# 10_iMX_8X_ETH.net
KiCad netlist of a schematic drawn in Altium Designer
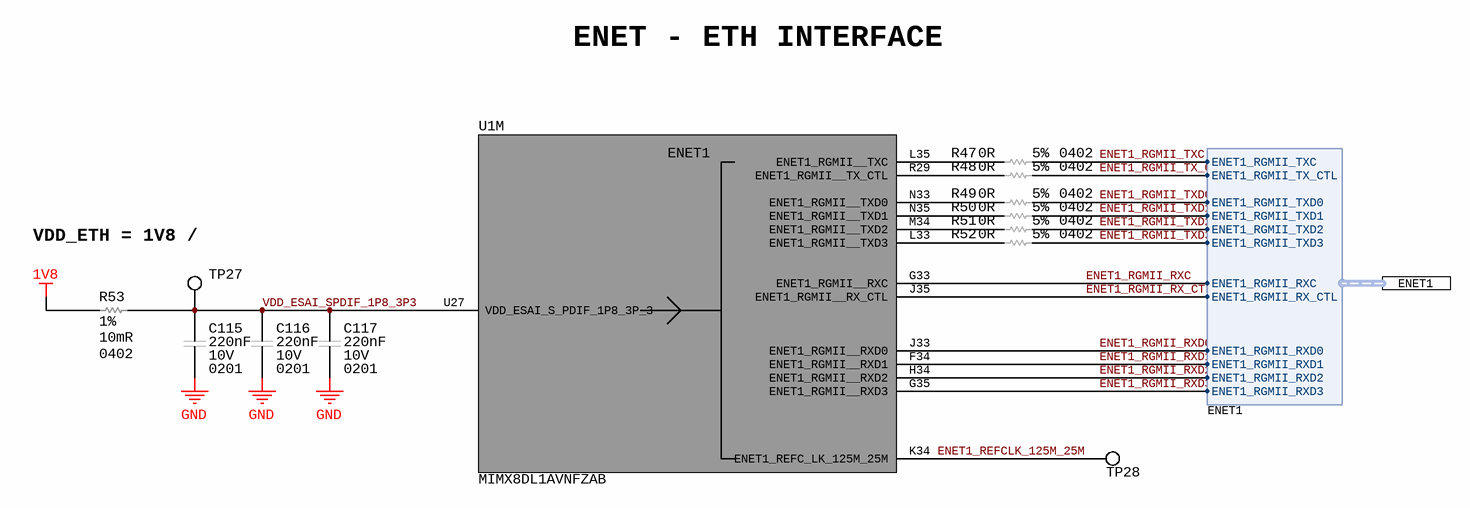
[diagram p0: 10_iMX 8X_ETH.SchDoc]

(export (version "E")
  (design (tool "Eeschema 10.0.6"))
  (components
    (comp (ref "C115")
      (value "LMK063BJ224MP-F")
      (footprint "CAP_0201_CAPC0603X03N")
      (description "Multilayer Ceramic Capacitors (High dielectric type), 10V, 0.22 uF, ± 20 %, 0201, X5R, RoHS")
      (fields
        (field (name "MANUFACTURER") "Taiyo Yuden")
        (field (name "TOLERANCE") "20%")
        (field (name "VOLTAGE RATING (DC)") "10V")
        (field (name "CAPACITANCE") "220nF")
        (field (name "CASE/PACKAGE") "0201")
      )
      (libsource (lib "Electronic Devices_LIB") (part "CAP_0.22UF_10V_X5R_0201"))
    )
    (comp (ref "C116")
      (value "LMK063BJ224MP-F")
      (footprint "CAP_0201_CAPC0603X03N")
      (description "Multilayer Ceramic Capacitors (High dielectric type), 10V, 0.22 uF, ± 20 %, 0201, X5R, RoHS")
      (fields
        (field (name "MANUFACTURER") "Taiyo Yuden")
        (field (name "TOLERANCE") "20%")
        (field (name "VOLTAGE RATING (DC)") "10V")
        (field (name "CAPACITANCE") "220nF")
        (field (name "CASE/PACKAGE") "0201")
      )
      (libsource (lib "Electronic Devices_LIB") (part "CAP_0.22UF_10V_X5R_0201"))
    )
    (comp (ref "C117")
      (value "LMK063BJ224MP-F")
      (footprint "CAP_0201_CAPC0603X03N")
      (description "Multilayer Ceramic Capacitors (High dielectric type), 10V, 0.22 uF, ± 20 %, 0201, X5R, RoHS")
      (fields
        (field (name "MANUFACTURER") "Taiyo Yuden")
        (field (name "TOLERANCE") "20%")
        (field (name "VOLTAGE RATING (DC)") "10V")
        (field (name "CAPACITANCE") "220nF")
        (field (name "CASE/PACKAGE") "0201")
      )
      (libsource (lib "Electronic Devices_LIB") (part "CAP_0.22UF_10V_X5R_0201"))
    )
    (comp (ref "R47")
      (value "ERJ-2GE0R00X")
      (footprint "RES_0402_RESC1005X04N")
      (description "SMD Chip Resistor, Jumper, 0 ohm, 100 mW, 0402 [1005 Metric], Thick Film, General Purpose")
      (fields
        (field (name "MANUFACTURER") "Panasonic")
        (field (name "CASE CODE (IMPERIAL)") "0402")
        (field (name "TOLERANCE") "5%")
        (field (name "RESISTANCE") "0R")
      )
      (libsource (lib "Electronic Devices_LIB") (part "RES_0R_5%_100mW_0402"))
    )
    (comp (ref "R48")
      (value "ERJ-2GE0R00X")
      (footprint "RES_0402_RESC1005X04N")
      (description "SMD Chip Resistor, Jumper, 0 ohm, 100 mW, 0402 [1005 Metric], Thick Film, General Purpose")
      (fields
        (field (name "MANUFACTURER") "Panasonic")
        (field (name "CASE CODE (IMPERIAL)") "0402")
        (field (name "TOLERANCE") "5%")
        (field (name "RESISTANCE") "0R")
      )
      (libsource (lib "Electronic Devices_LIB") (part "RES_0R_5%_100mW_0402"))
    )
    (comp (ref "R49")
      (value "ERJ-2GE0R00X")
      (footprint "RES_0402_RESC1005X04N")
      (description "SMD Chip Resistor, Jumper, 0 ohm, 100 mW, 0402 [1005 Metric], Thick Film, General Purpose")
      (fields
        (field (name "MANUFACTURER") "Panasonic")
        (field (name "CASE CODE (IMPERIAL)") "0402")
        (field (name "TOLERANCE") "5%")
        (field (name "RESISTANCE") "0R")
      )
      (libsource (lib "Electronic Devices_LIB") (part "RES_0R_5%_100mW_0402"))
    )
    (comp (ref "R50")
      (value "ERJ-2GE0R00X")
      (footprint "RES_0402_RESC1005X04N")
      (description "SMD Chip Resistor, Jumper, 0 ohm, 100 mW, 0402 [1005 Metric], Thick Film, General Purpose")
      (fields
        (field (name "MANUFACTURER") "Panasonic")
        (field (name "CASE CODE (IMPERIAL)") "0402")
        (field (name "TOLERANCE") "5%")
        (field (name "RESISTANCE") "0R")
      )
      (libsource (lib "Electronic Devices_LIB") (part "RES_0R_5%_100mW_0402"))
    )
    (comp (ref "R51")
      (value "ERJ-2GE0R00X")
      (footprint "RES_0402_RESC1005X04N")
      (description "SMD Chip Resistor, Jumper, 0 ohm, 100 mW, 0402 [1005 Metric], Thick Film, General Purpose")
      (fields
        (field (name "MANUFACTURER") "Panasonic")
        (field (name "CASE CODE (IMPERIAL)") "0402")
        (field (name "TOLERANCE") "5%")
        (field (name "RESISTANCE") "0R")
      )
      (libsource (lib "Electronic Devices_LIB") (part "RES_0R_5%_100mW_0402"))
    )
    (comp (ref "R52")
      (value "ERJ-2GE0R00X")
      (footprint "RES_0402_RESC1005X04N")
      (description "SMD Chip Resistor, Jumper, 0 ohm, 100 mW, 0402 [1005 Metric], Thick Film, General Purpose")
      (fields
        (field (name "MANUFACTURER") "Panasonic")
        (field (name "CASE CODE (IMPERIAL)") "0402")
        (field (name "TOLERANCE") "5%")
        (field (name "RESISTANCE") "0R")
      )
      (libsource (lib "Electronic Devices_LIB") (part "RES_0R_5%_100mW_0402"))
    )
    (comp (ref "R53")
      (value "ERJ-2LWFR010X")
      (footprint "RES_0603_RESC1608X04N")
      (description "Res Current Sense Thick Film 0402 0.01 Ohm 1% 1/5W 0ppm/°C to 500ppm/°C Molded T/R")
      (fields
        (field (name "MANUFACTURER") "Panasonic")
        (field (name "TOLERANCE") "1%")
        (field (name "RESISTANCE") "10mR")
        (field (name "CASE/PACKAGE") "0402")
      )
      (libsource (lib "Electronic Devices_LIB") (part "RES_10mR_1%_0.05W_0402"))
    )
    (comp (ref "TP27")
      (value "NO COMPONENT")
      (footprint "TP_PAD_0.5MM_SMD_ROUND")
      (description "Test Point, SMD pad, round, 1.5mm, 1.6mm, 3mm diameter")
      (libsource (lib "Electronic Devices_LIB") (part "TP_PAD_SMD_SMALL"))
    )
    (comp (ref "TP28")
      (value "NO COMPONENT")
      (footprint "TP_PAD_0.5MM_SMD_ROUND")
      (description "Test Point, SMD pad, round, 1.5mm, 1.6mm, 3mm diameter")
      (libsource (lib "Electronic Devices_LIB") (part "TP_PAD_SMD_SMALL"))
    )
    (comp (ref "U1")
      (value "MIMX8DL1AVNFZAB")
      (footprint "MIMX8DL1AVNFZAB")
      (description "I.MX8 Dxl 15SQ / Tray Rohs Compliant: Yes")
      (fields (field (name "MANUFACTURER") "NXP Semiconductors"))
      (libsource (lib "Electronic Devices_LIB") (part "IC_MPU_ARM_1.2GHz_MIMX8DL1AVNFZAB"))
    )
  )
  (nets
    (net (code "2") (name "/ENET1_REFCLK_125M_25M") (class "Default")
      (node (ref "TP28") (pin "1") (pinfunction "1_1") (pintype "passive"))
      (node (ref "U1") (pin "K34") (pinfunction "ENET1_REFC_LK_125M_25M_K34") (pintype "passive"))
    )
    (net (code "3") (name "/ENET1_RGMII_RXC") (class "Default")
      (node (ref "U1") (pin "G33") (pinfunction "ENET1_RGMII__RXC_G33") (pintype "passive"))
    )
    (net (code "4") (name "/ENET1_RGMII_RXD0") (class "Default")
      (node (ref "U1") (pin "J33") (pinfunction "ENET1_RGMII__RXD0_J33") (pintype "passive"))
    )
    (net (code "5") (name "/ENET1_RGMII_RXD1") (class "Default")
      (node (ref "U1") (pin "F34") (pinfunction "ENET1_RGMII__RXD1_F34") (pintype "passive"))
    )
    (net (code "6") (name "/ENET1_RGMII_RXD2") (class "Default")
      (node (ref "U1") (pin "H34") (pinfunction "ENET1_RGMII__RXD2_H34") (pintype "passive"))
    )
    (net (code "7") (name "/ENET1_RGMII_RXD3") (class "Default")
      (node (ref "U1") (pin "G35") (pinfunction "ENET1_RGMII__RXD3_G35") (pintype "passive"))
    )
    (net (code "8") (name "/ENET1_RGMII_RX_CTL") (class "Default")
      (node (ref "U1") (pin "J35") (pinfunction "ENET1_RGMII__RX_CTL_J35") (pintype "passive"))
    )
    (net (code "9") (name "/ENET1_RGMII_TXC") (class "Default")
      (node (ref "R47") (pin "2") (pinfunction "2_2") (pintype "passive"))
    )
    (net (code "10") (name "/ENET1_RGMII_TXD0") (class "Default")
      (node (ref "R49") (pin "2") (pinfunction "2_2") (pintype "passive"))
    )
    (net (code "11") (name "/ENET1_RGMII_TXD1") (class "Default")
      (node (ref "R50") (pin "2") (pinfunction "2_2") (pintype "passive"))
    )
    (net (code "12") (name "/ENET1_RGMII_TXD2") (class "Default")
      (node (ref "R51") (pin "2") (pinfunction "2_2") (pintype "passive"))
    )
    (net (code "13") (name "/ENET1_RGMII_TXD3") (class "Default")
      (node (ref "R52") (pin "2") (pinfunction "2_2") (pintype "passive"))
    )
    (net (code "14") (name "/ENET1_RGMII_TX_CTL") (class "Default")
      (node (ref "R48") (pin "2") (pinfunction "2_2") (pintype "passive"))
    )
    (net (code "15") (name "/VDD_ESAI_SPDIF_1P8_3P3") (class "Default")
      (node (ref "C115") (pin "2") (pinfunction "2_2") (pintype "passive"))
      (node (ref "C116") (pin "2") (pinfunction "2_2") (pintype "passive"))
      (node (ref "C117") (pin "2") (pinfunction "2_2") (pintype "passive"))
      (node (ref "R53") (pin "2") (pinfunction "2_2") (pintype "passive"))
      (node (ref "TP27") (pin "1") (pinfunction "1_1") (pintype "passive"))
      (node (ref "U1") (pin "U27") (pinfunction "VDD_ESAI_S_PDIF_1P8_3P_3_U27") (pintype "passive"))
    )
    (net (code "17") (name "1V8") (class "Default")
      (node (ref "R53") (pin "1") (pinfunction "1_1") (pintype "passive"))
    )
    (net (code "18") (name "GND") (class "Default")
      (node (ref "C115") (pin "1") (pinfunction "1_1") (pintype "passive"))
      (node (ref "C116") (pin "1") (pinfunction "1_1") (pintype "passive"))
      (node (ref "C117") (pin "1") (pinfunction "1_1") (pintype "passive"))
    )
    (net (code "19") (name "Net-(U1M-ENET1_RGMII__TXC)") (class "Default")
      (node (ref "R47") (pin "1") (pinfunction "1_1") (pintype "passive"))
      (node (ref "U1") (pin "L35") (pinfunction "ENET1_RGMII__TXC_L35") (pintype "passive"))
    )
    (net (code "20") (name "Net-(U1M-ENET1_RGMII__TXD0)") (class "Default")
      (node (ref "R49") (pin "1") (pinfunction "1_1") (pintype "passive"))
      (node (ref "U1") (pin "N33") (pinfunction "ENET1_RGMII__TXD0_N33") (pintype "passive"))
    )
    (net (code "21") (name "Net-(U1M-ENET1_RGMII__TXD1)") (class "Default")
      (node (ref "R50") (pin "1") (pinfunction "1_1") (pintype "passive"))
      (node (ref "U1") (pin "N35") (pinfunction "ENET1_RGMII__TXD1_N35") (pintype "passive"))
    )
    (net (code "22") (name "Net-(U1M-ENET1_RGMII__TXD2)") (class "Default")
      (node (ref "R51") (pin "1") (pinfunction "1_1") (pintype "passive"))
      (node (ref "U1") (pin "M34") (pinfunction "ENET1_RGMII__TXD2_M34") (pintype "passive"))
    )
    (net (code "23") (name "Net-(U1M-ENET1_RGMII__TXD3)") (class "Default")
      (node (ref "R52") (pin "1") (pinfunction "1_1") (pintype "passive"))
      (node (ref "U1") (pin "L33") (pinfunction "ENET1_RGMII__TXD3_L33") (pintype "passive"))
    )
    (net (code "24") (name "Net-(U1M-ENET1_RGMII__TX_CTL)") (class "Default")
      (node (ref "R48") (pin "1") (pinfunction "1_1") (pintype "passive"))
      (node (ref "U1") (pin "R29") (pinfunction "ENET1_RGMII__TX_CTL_R29") (pintype "passive"))
    )
  )
)
